# PowerBoard.net
KiCad netlist of a schematic drawn in Altium Designer
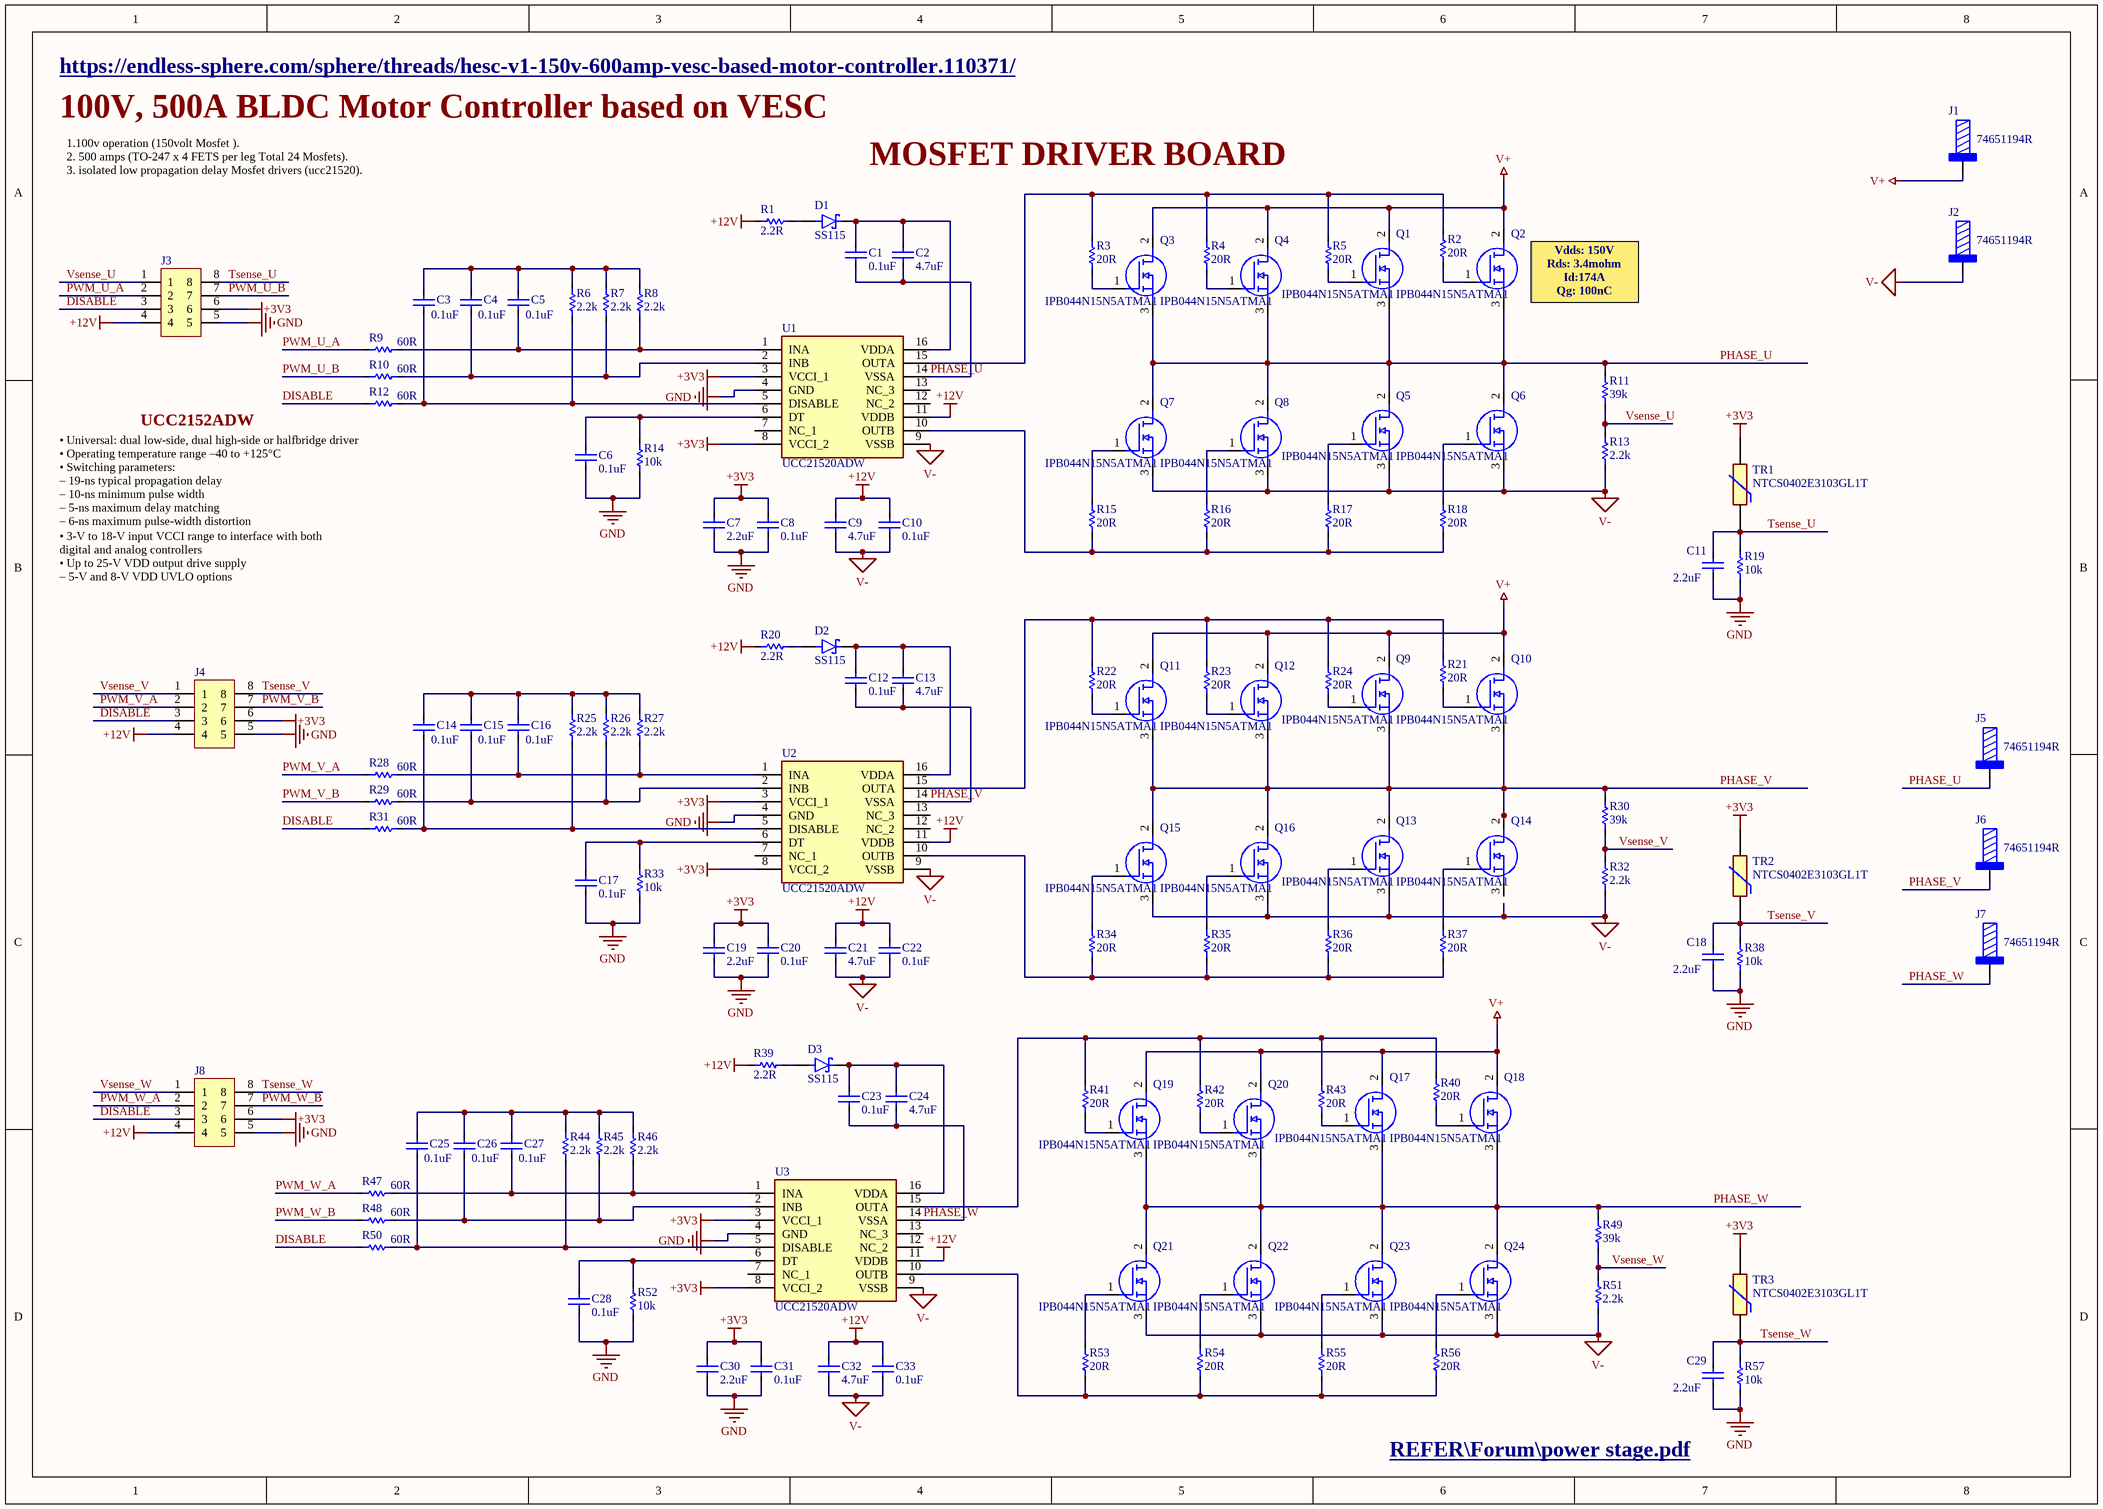
[diagram p0: PowerBoard.SchDoc]

(export (version "E")
  (design (tool "Eeschema 10.0.6"))
  (components
    (comp (ref "C1")
      (value "0.1uF")
      (footprint "SMD_C(0402)")
      (description "Multilayer Ceramic Capacitors MLCC - SMD/SMT 50 V 0.1uF X7R 0603 10%")
      (fields
        (field (name "MANUFACTURER") "Yageo")
        (field (name "MANUFACTURER PART NUMBER") "CC0603KPX7R9BB104")
      )
      (libsource (lib "CameraBoard") (part "Cap_1"))
    )
    (comp (ref "C2")
      (value "4.7uF")
      (footprint "SMD_C(0603)")
      (description "PHE840MA6100MA04R17")
      (fields
        (field (name "MANUFACTURER") "Yageo")
        (field (name "MANUFACTURER PART NUMBER") "CC0603KPX7R9BB104")
      )
      (libsource (lib "CameraBoard") (part "Cap_10"))
    )
    (comp (ref "C3")
      (value "0.1uF")
      (footprint "SMD_C(0402)")
      (description "Multilayer Ceramic Capacitors MLCC - SMD/SMT 50 V 0.1uF X7R 0603 10%")
      (fields
        (field (name "MANUFACTURER") "Yageo")
        (field (name "MANUFACTURER PART NUMBER") "CC0603KPX7R9BB104")
      )
      (libsource (lib "CameraBoard") (part "Cap_1"))
    )
    (comp (ref "C4")
      (value "0.1uF")
      (footprint "SMD_C(0402)")
      (description "Multilayer Ceramic Capacitors MLCC - SMD/SMT 50 V 0.1uF X7R 0603 10%")
      (fields
        (field (name "MANUFACTURER") "Yageo")
        (field (name "MANUFACTURER PART NUMBER") "CC0603KPX7R9BB104")
      )
      (libsource (lib "CameraBoard") (part "Cap_1"))
    )
    (comp (ref "C5")
      (value "0.1uF")
      (footprint "SMD_C(0402)")
      (description "Multilayer Ceramic Capacitors MLCC - SMD/SMT 50 V 0.1uF X7R 0603 10%")
      (fields
        (field (name "MANUFACTURER") "Yageo")
        (field (name "MANUFACTURER PART NUMBER") "CC0603KPX7R9BB104")
      )
      (libsource (lib "CameraBoard") (part "Cap_1"))
    )
    (comp (ref "C6")
      (value "0.1uF")
      (footprint "SMD_C(0402)")
      (description "Multilayer Ceramic Capacitors MLCC - SMD/SMT 50 V 0.1uF X7R 0603 10%")
      (fields
        (field (name "MANUFACTURER") "Yageo")
        (field (name "MANUFACTURER PART NUMBER") "CC0603KPX7R9BB104")
      )
      (libsource (lib "CameraBoard") (part "Cap_1"))
    )
    (comp (ref "C7")
      (value "2.2uF")
      (footprint "SMD_C(0603)")
      (description "PHE840MA6100MA04R17")
      (fields
        (field (name "MANUFACTURER") "Yageo")
        (field (name "MANUFACTURER PART NUMBER") "CC0603KPX7R9BB104")
      )
      (libsource (lib "CameraBoard") (part "Cap_10"))
    )
    (comp (ref "C8")
      (value "0.1uF")
      (footprint "SMD_C(0402)")
      (description "Multilayer Ceramic Capacitors MLCC - SMD/SMT 50 V 0.1uF X7R 0603 10%")
      (fields
        (field (name "MANUFACTURER") "Yageo")
        (field (name "MANUFACTURER PART NUMBER") "CC0603KPX7R9BB104")
      )
      (libsource (lib "CameraBoard") (part "Cap_1"))
    )
    (comp (ref "C9")
      (value "4.7uF")
      (footprint "SMD_C(0603)")
      (description "PHE840MA6100MA04R17")
      (fields
        (field (name "MANUFACTURER") "Yageo")
        (field (name "MANUFACTURER PART NUMBER") "CC0603KPX7R9BB104")
      )
      (libsource (lib "CameraBoard") (part "Cap_10"))
    )
    (comp (ref "C10")
      (value "0.1uF")
      (footprint "SMD_C(0402)")
      (description "Multilayer Ceramic Capacitors MLCC - SMD/SMT 50 V 0.1uF X7R 0603 10%")
      (fields
        (field (name "MANUFACTURER") "Yageo")
        (field (name "MANUFACTURER PART NUMBER") "CC0603KPX7R9BB104")
      )
      (libsource (lib "CameraBoard") (part "Cap_1"))
    )
    (comp (ref "C11")
      (value "2.2uF")
      (footprint "SMD_C(0402)")
      (description "Multilayer Ceramic Capacitors MLCC - SMD/SMT 50 V 0.1uF X7R 0603 10%")
      (libsource (lib "CameraBoard") (part "Cap_1"))
    )
    (comp (ref "C12")
      (value "0.1uF")
      (footprint "SMD_C(0402)")
      (description "Multilayer Ceramic Capacitors MLCC - SMD/SMT 50 V 0.1uF X7R 0603 10%")
      (fields
        (field (name "MANUFACTURER") "Yageo")
        (field (name "MANUFACTURER PART NUMBER") "CC0603KPX7R9BB104")
      )
      (libsource (lib "CameraBoard") (part "Cap_1"))
    )
    (comp (ref "C13")
      (value "4.7uF")
      (footprint "SMD_C(0603)")
      (description "PHE840MA6100MA04R17")
      (fields
        (field (name "MANUFACTURER") "Yageo")
        (field (name "MANUFACTURER PART NUMBER") "CC0603KPX7R9BB104")
      )
      (libsource (lib "CameraBoard") (part "Cap_10"))
    )
    (comp (ref "C14")
      (value "0.1uF")
      (footprint "SMD_C(0402)")
      (description "Multilayer Ceramic Capacitors MLCC - SMD/SMT 50 V 0.1uF X7R 0603 10%")
      (fields
        (field (name "MANUFACTURER") "Yageo")
        (field (name "MANUFACTURER PART NUMBER") "CC0603KPX7R9BB104")
      )
      (libsource (lib "CameraBoard") (part "Cap_1"))
    )
    (comp (ref "C15")
      (value "0.1uF")
      (footprint "SMD_C(0402)")
      (description "Multilayer Ceramic Capacitors MLCC - SMD/SMT 50 V 0.1uF X7R 0603 10%")
      (fields
        (field (name "MANUFACTURER") "Yageo")
        (field (name "MANUFACTURER PART NUMBER") "CC0603KPX7R9BB104")
      )
      (libsource (lib "CameraBoard") (part "Cap_1"))
    )
    (comp (ref "C16")
      (value "0.1uF")
      (footprint "SMD_C(0402)")
      (description "Multilayer Ceramic Capacitors MLCC - SMD/SMT 50 V 0.1uF X7R 0603 10%")
      (fields
        (field (name "MANUFACTURER") "Yageo")
        (field (name "MANUFACTURER PART NUMBER") "CC0603KPX7R9BB104")
      )
      (libsource (lib "CameraBoard") (part "Cap_1"))
    )
    (comp (ref "C17")
      (value "0.1uF")
      (footprint "SMD_C(0402)")
      (description "Multilayer Ceramic Capacitors MLCC - SMD/SMT 50 V 0.1uF X7R 0603 10%")
      (fields
        (field (name "MANUFACTURER") "Yageo")
        (field (name "MANUFACTURER PART NUMBER") "CC0603KPX7R9BB104")
      )
      (libsource (lib "CameraBoard") (part "Cap_1"))
    )
    (comp (ref "C18")
      (value "2.2uF")
      (footprint "SMD_C(0402)")
      (description "Multilayer Ceramic Capacitors MLCC - SMD/SMT 50 V 0.1uF X7R 0603 10%")
      (libsource (lib "CameraBoard") (part "Cap_1"))
    )
    (comp (ref "C19")
      (value "2.2uF")
      (footprint "SMD_C(0603)")
      (description "PHE840MA6100MA04R17")
      (fields
        (field (name "MANUFACTURER") "Yageo")
        (field (name "MANUFACTURER PART NUMBER") "CC0603KPX7R9BB104")
      )
      (libsource (lib "CameraBoard") (part "Cap_10"))
    )
    (comp (ref "C20")
      (value "0.1uF")
      (footprint "SMD_C(0402)")
      (description "Multilayer Ceramic Capacitors MLCC - SMD/SMT 50 V 0.1uF X7R 0603 10%")
      (fields
        (field (name "MANUFACTURER") "Yageo")
        (field (name "MANUFACTURER PART NUMBER") "CC0603KPX7R9BB104")
      )
      (libsource (lib "CameraBoard") (part "Cap_1"))
    )
    (comp (ref "C21")
      (value "4.7uF")
      (footprint "SMD_C(0603)")
      (description "PHE840MA6100MA04R17")
      (fields
        (field (name "MANUFACTURER") "Yageo")
        (field (name "MANUFACTURER PART NUMBER") "CC0603KPX7R9BB104")
      )
      (libsource (lib "CameraBoard") (part "Cap_10"))
    )
    (comp (ref "C22")
      (value "0.1uF")
      (footprint "SMD_C(0402)")
      (description "Multilayer Ceramic Capacitors MLCC - SMD/SMT 50 V 0.1uF X7R 0603 10%")
      (fields
        (field (name "MANUFACTURER") "Yageo")
        (field (name "MANUFACTURER PART NUMBER") "CC0603KPX7R9BB104")
      )
      (libsource (lib "CameraBoard") (part "Cap_1"))
    )
    (comp (ref "C23")
      (value "0.1uF")
      (footprint "SMD_C(0402)")
      (description "Multilayer Ceramic Capacitors MLCC - SMD/SMT 50 V 0.1uF X7R 0603 10%")
      (fields
        (field (name "MANUFACTURER") "Yageo")
        (field (name "MANUFACTURER PART NUMBER") "CC0603KPX7R9BB104")
      )
      (libsource (lib "CameraBoard") (part "Cap_1"))
    )
    (comp (ref "C24")
      (value "4.7uF")
      (footprint "SMD_C(0603)")
      (description "PHE840MA6100MA04R17")
      (fields
        (field (name "MANUFACTURER") "Yageo")
        (field (name "MANUFACTURER PART NUMBER") "CC0603KPX7R9BB104")
      )
      (libsource (lib "CameraBoard") (part "Cap_10"))
    )
    (comp (ref "C25")
      (value "0.1uF")
      (footprint "SMD_C(0402)")
      (description "Multilayer Ceramic Capacitors MLCC - SMD/SMT 50 V 0.1uF X7R 0603 10%")
      (fields
        (field (name "MANUFACTURER") "Yageo")
        (field (name "MANUFACTURER PART NUMBER") "CC0603KPX7R9BB104")
      )
      (libsource (lib "CameraBoard") (part "Cap_1"))
    )
    (comp (ref "C26")
      (value "0.1uF")
      (footprint "SMD_C(0402)")
      (description "Multilayer Ceramic Capacitors MLCC - SMD/SMT 50 V 0.1uF X7R 0603 10%")
      (fields
        (field (name "MANUFACTURER") "Yageo")
        (field (name "MANUFACTURER PART NUMBER") "CC0603KPX7R9BB104")
      )
      (libsource (lib "CameraBoard") (part "Cap_1"))
    )
    (comp (ref "C27")
      (value "0.1uF")
      (footprint "SMD_C(0402)")
      (description "Multilayer Ceramic Capacitors MLCC - SMD/SMT 50 V 0.1uF X7R 0603 10%")
      (fields
        (field (name "MANUFACTURER") "Yageo")
        (field (name "MANUFACTURER PART NUMBER") "CC0603KPX7R9BB104")
      )
      (libsource (lib "CameraBoard") (part "Cap_1"))
    )
    (comp (ref "C28")
      (value "0.1uF")
      (footprint "SMD_C(0402)")
      (description "Multilayer Ceramic Capacitors MLCC - SMD/SMT 50 V 0.1uF X7R 0603 10%")
      (fields
        (field (name "MANUFACTURER") "Yageo")
        (field (name "MANUFACTURER PART NUMBER") "CC0603KPX7R9BB104")
      )
      (libsource (lib "CameraBoard") (part "Cap_1"))
    )
    (comp (ref "C29")
      (value "2.2uF")
      (footprint "SMD_C(0402)")
      (description "Multilayer Ceramic Capacitors MLCC - SMD/SMT 50 V 0.1uF X7R 0603 10%")
      (libsource (lib "CameraBoard") (part "Cap_1"))
    )
    (comp (ref "C30")
      (value "2.2uF")
      (footprint "SMD_C(0603)")
      (description "PHE840MA6100MA04R17")
      (fields
        (field (name "MANUFACTURER") "Yageo")
        (field (name "MANUFACTURER PART NUMBER") "CC0603KPX7R9BB104")
      )
      (libsource (lib "CameraBoard") (part "Cap_10"))
    )
    (comp (ref "C31")
      (value "0.1uF")
      (footprint "SMD_C(0402)")
      (description "Multilayer Ceramic Capacitors MLCC - SMD/SMT 50 V 0.1uF X7R 0603 10%")
      (fields
        (field (name "MANUFACTURER") "Yageo")
        (field (name "MANUFACTURER PART NUMBER") "CC0603KPX7R9BB104")
      )
      (libsource (lib "CameraBoard") (part "Cap_1"))
    )
    (comp (ref "C32")
      (value "4.7uF")
      (footprint "SMD_C(0603)")
      (description "PHE840MA6100MA04R17")
      (fields
        (field (name "MANUFACTURER") "Yageo")
        (field (name "MANUFACTURER PART NUMBER") "CC0603KPX7R9BB104")
      )
      (libsource (lib "CameraBoard") (part "Cap_10"))
    )
    (comp (ref "C33")
      (value "0.1uF")
      (footprint "SMD_C(0402)")
      (description "Multilayer Ceramic Capacitors MLCC - SMD/SMT 50 V 0.1uF X7R 0603 10%")
      (fields
        (field (name "MANUFACTURER") "Yageo")
        (field (name "MANUFACTURER PART NUMBER") "CC0603KPX7R9BB104")
      )
      (libsource (lib "CameraBoard") (part "Cap_1"))
    )
    (comp (ref "D1")
      (value "SS115")
      (footprint "DIOM4325X250N")
      (description "1A, 150V, Schottky Rectifier")
      (fields (field (name "MF") "Taiwan Semiconductor"))
      (libsource (lib "SS115") (part "SS115"))
    )
    (comp (ref "D2")
      (value "SS115")
      (footprint "DIOM4325X250N")
      (description "1A, 150V, Schottky Rectifier")
      (fields (field (name "MF") "Taiwan Semiconductor"))
      (libsource (lib "SS115") (part "SS115"))
    )
    (comp (ref "D3")
      (value "SS115")
      (footprint "DIOM4325X250N")
      (description "1A, 150V, Schottky Rectifier")
      (fields (field (name "MF") "Taiwan Semiconductor"))
      (libsource (lib "SS115") (part "SS115"))
    )
    (comp (ref "J1")
      (value "74651194R")
      (footprint "74651194")
      (description "WP-THRSH REDCUBE THR with external thread, M4 x 5mm, 85A")
      (fields (field (name "MANUFACTURER") "Wurth Elektronik"))
      (libsource (lib "WP-THRSH") (part "74651194R"))
    )
    (comp (ref "J2")
      (value "74651194R")
      (footprint "74651194")
      (description "WP-THRSH REDCUBE THR with external thread, M4 x 5mm, 85A")
      (fields (field (name "MANUFACTURER") "Wurth Elektronik"))
      (libsource (lib "WP-THRSH") (part "74651194R"))
    )
    (comp (ref "J3")
      (value "~")
      (footprint "*")
      (description "2 Row 2.54mm Pitch 8 pins")
      (libsource (lib "VESC_MotorController") (part "PCB Header"))
    )
    (comp (ref "J4")
      (value "~")
      (footprint "*")
      (description "2 Row 2.54mm Pitch 8 pins")
      (libsource (lib "VESC_MotorController") (part "PCB Header"))
    )
    (comp (ref "J5")
      (value "74651194R")
      (footprint "74651194")
      (description "WP-THRSH REDCUBE THR with external thread, M4 x 5mm, 85A")
      (fields (field (name "MANUFACTURER") "Wurth Elektronik"))
      (libsource (lib "WP-THRSH") (part "74651194R"))
    )
    (comp (ref "J6")
      (value "74651194R")
      (footprint "74651194")
      (description "WP-THRSH REDCUBE THR with external thread, M4 x 5mm, 85A")
      (fields (field (name "MANUFACTURER") "Wurth Elektronik"))
      (libsource (lib "WP-THRSH") (part "74651194R"))
    )
    (comp (ref "J7")
      (value "74651194R")
      (footprint "74651194")
      (description "WP-THRSH REDCUBE THR with external thread, M4 x 5mm, 85A")
      (fields (field (name "MANUFACTURER") "Wurth Elektronik"))
      (libsource (lib "WP-THRSH") (part "74651194R"))
    )
    (comp (ref "J8")
      (value "~")
      (footprint "*")
      (description "2 Row 2.54mm Pitch 8 pins")
      (libsource (lib "VESC_MotorController") (part "PCB Header"))
    )
    (comp (ref "Q1")
      (value "IPB044N15N5ATMA1")
      (footprint "TO546P531X1558X2499-3P")
      (description "MOSFET N-CHANNEL 100+")
      (fields
        (field (name "MOUSER PART NUMBER") "942-AUIRFP4568")
        (field (name "MANUFACTURER_PART_NUMBER") "AUIRFP4568")
      )
      (libsource (lib "AUIRFP4568") (part "AUIRFP4568"))
    )
    (comp (ref "Q2")
      (value "IPB044N15N5ATMA1")
      (footprint "TO546P531X1558X2499-3P")
      (description "MOSFET N-CHANNEL 100+")
      (fields
        (field (name "MOUSER PART NUMBER") "942-AUIRFP4568")
        (field (name "MANUFACTURER_PART_NUMBER") "AUIRFP4568")
      )
      (libsource (lib "AUIRFP4568") (part "AUIRFP4568"))
    )
    (comp (ref "Q3")
      (value "IPB044N15N5ATMA1")
      (footprint "TO546P531X1558X2499-3P")
      (description "MOSFET N-CHANNEL 100+")
      (fields
        (field (name "MOUSER PART NUMBER") "942-AUIRFP4568")
        (field (name "MANUFACTURER_PART_NUMBER") "AUIRFP4568")
      )
      (libsource (lib "AUIRFP4568") (part "AUIRFP4568"))
    )
    (comp (ref "Q4")
      (value "IPB044N15N5ATMA1")
      (footprint "TO546P531X1558X2499-3P")
      (description "MOSFET N-CHANNEL 100+")
      (fields
        (field (name "MOUSER PART NUMBER") "942-AUIRFP4568")
        (field (name "MANUFACTURER_PART_NUMBER") "AUIRFP4568")
      )
      (libsource (lib "AUIRFP4568") (part "AUIRFP4568"))
    )
    (comp (ref "Q5")
      (value "IPB044N15N5ATMA1")
      (footprint "TO546P531X1558X2499-3P")
      (description "MOSFET N-CHANNEL 100+")
      (fields
        (field (name "MOUSER PART NUMBER") "942-AUIRFP4568")
        (field (name "MANUFACTURER_PART_NUMBER") "AUIRFP4568")
      )
      (libsource (lib "AUIRFP4568") (part "AUIRFP4568"))
    )
    (comp (ref "Q6")
      (value "IPB044N15N5ATMA1")
      (footprint "TO546P531X1558X2499-3P")
      (description "MOSFET N-CHANNEL 100+")
      (fields
        (field (name "MOUSER PART NUMBER") "942-AUIRFP4568")
        (field (name "MANUFACTURER_PART_NUMBER") "AUIRFP4568")
      )
      (libsource (lib "AUIRFP4568") (part "AUIRFP4568"))
    )
    (comp (ref "Q7")
      (value "IPB044N15N5ATMA1")
      (footprint "TO546P531X1558X2499-3P")
      (description "MOSFET N-CHANNEL 100+")
      (fields
        (field (name "MOUSER PART NUMBER") "942-AUIRFP4568")
        (field (name "MANUFACTURER_PART_NUMBER") "AUIRFP4568")
      )
      (libsource (lib "AUIRFP4568") (part "AUIRFP4568"))
    )
    (comp (ref "Q8")
      (value "IPB044N15N5ATMA1")
      (footprint "TO546P531X1558X2499-3P")
      (description "MOSFET N-CHANNEL 100+")
      (fields
        (field (name "MOUSER PART NUMBER") "942-AUIRFP4568")
        (field (name "MANUFACTURER_PART_NUMBER") "AUIRFP4568")
      )
      (libsource (lib "AUIRFP4568") (part "AUIRFP4568"))
    )
    (comp (ref "Q9")
      (value "IPB044N15N5ATMA1")
      (footprint "TO546P531X1558X2499-3P")
      (description "MOSFET N-CHANNEL 100+")
      (fields
        (field (name "MOUSER PART NUMBER") "942-AUIRFP4568")
        (field (name "MANUFACTURER_PART_NUMBER") "AUIRFP4568")
      )
      (libsource (lib "AUIRFP4568") (part "AUIRFP4568"))
    )
    (comp (ref "Q10")
      (value "IPB044N15N5ATMA1")
      (footprint "TO546P531X1558X2499-3P")
      (description "MOSFET N-CHANNEL 100+")
      (fields
        (field (name "MOUSER PART NUMBER") "942-AUIRFP4568")
        (field (name "MANUFACTURER_PART_NUMBER") "AUIRFP4568")
      )
      (libsource (lib "AUIRFP4568") (part "AUIRFP4568"))
    )
    (comp (ref "Q11")
      (value "IPB044N15N5ATMA1")
      (footprint "TO546P531X1558X2499-3P")
      (description "MOSFET N-CHANNEL 100+")
      (fields
        (field (name "MOUSER PART NUMBER") "942-AUIRFP4568")
        (field (name "MANUFACTURER_PART_NUMBER") "AUIRFP4568")
      )
      (libsource (lib "AUIRFP4568") (part "AUIRFP4568"))
    )
    (comp (ref "Q12")
      (value "IPB044N15N5ATMA1")
      (footprint "TO546P531X1558X2499-3P")
      (description "MOSFET N-CHANNEL 100+")
      (fields
        (field (name "MOUSER PART NUMBER") "942-AUIRFP4568")
        (field (name "MANUFACTURER_PART_NUMBER") "AUIRFP4568")
      )
      (libsource (lib "AUIRFP4568") (part "AUIRFP4568"))
    )
    (comp (ref "Q13")
      (value "IPB044N15N5ATMA1")
      (footprint "TO546P531X1558X2499-3P")
      (description "MOSFET N-CHANNEL 100+")
      (fields
        (field (name "MOUSER PART NUMBER") "942-AUIRFP4568")
        (field (name "MANUFACTURER_PART_NUMBER") "AUIRFP4568")
      )
      (libsource (lib "AUIRFP4568") (part "AUIRFP4568"))
    )
    (comp (ref "Q14")
      (value "IPB044N15N5ATMA1")
      (footprint "TO546P531X1558X2499-3P")
      (description "MOSFET N-CHANNEL 100+")
      (fields
        (field (name "MOUSER PART NUMBER") "942-AUIRFP4568")
        (field (name "MANUFACTURER_PART_NUMBER") "AUIRFP4568")
      )
      (libsource (lib "AUIRFP4568") (part "AUIRFP4568"))
    )
    (comp (ref "Q15")
      (value "IPB044N15N5ATMA1")
      (footprint "TO546P531X1558X2499-3P")
      (description "MOSFET N-CHANNEL 100+")
      (fields
        (field (name "MOUSER PART NUMBER") "942-AUIRFP4568")
        (field (name "MANUFACTURER_PART_NUMBER") "AUIRFP4568")
      )
      (libsource (lib "AUIRFP4568") (part "AUIRFP4568"))
    )
    (comp (ref "Q16")
      (value "IPB044N15N5ATMA1")
      (footprint "TO546P531X1558X2499-3P")
      (description "MOSFET N-CHANNEL 100+")
      (fields
        (field (name "MOUSER PART NUMBER") "942-AUIRFP4568")
        (field (name "MANUFACTURER_PART_NUMBER") "AUIRFP4568")
      )
      (libsource (lib "AUIRFP4568") (part "AUIRFP4568"))
    )
    (comp (ref "Q17")
      (value "IPB044N15N5ATMA1")
      (footprint "TO546P531X1558X2499-3P")
      (description "MOSFET N-CHANNEL 100+")
      (fields
        (field (name "MOUSER PART NUMBER") "942-AUIRFP4568")
        (field (name "MANUFACTURER_PART_NUMBER") "AUIRFP4568")
      )
      (libsource (lib "AUIRFP4568") (part "AUIRFP4568"))
    )
    (comp (ref "Q18")
      (value "IPB044N15N5ATMA1")
      (footprint "TO546P531X1558X2499-3P")
      (description "MOSFET N-CHANNEL 100+")
      (fields
        (field (name "MOUSER PART NUMBER") "942-AUIRFP4568")
        (field (name "MANUFACTURER_PART_NUMBER") "AUIRFP4568")
      )
      (libsource (lib "AUIRFP4568") (part "AUIRFP4568"))
    )
    (comp (ref "Q19")
      (value "IPB044N15N5ATMA1")
      (footprint "TO546P531X1558X2499-3P")
      (description "MOSFET N-CHANNEL 100+")
      (fields
        (field (name "MOUSER PART NUMBER") "942-AUIRFP4568")
        (field (name "MANUFACTURER_PART_NUMBER") "AUIRFP4568")
      )
      (libsource (lib "AUIRFP4568") (part "AUIRFP4568"))
    )
    (comp (ref "Q20")
      (value "IPB044N15N5ATMA1")
      (footprint "TO546P531X1558X2499-3P")
      (description "MOSFET N-CHANNEL 100+")
      (fields
        (field (name "MOUSER PART NUMBER") "942-AUIRFP4568")
        (field (name "MANUFACTURER_PART_NUMBER") "AUIRFP4568")
      )
      (libsource (lib "AUIRFP4568") (part "AUIRFP4568"))
    )
    (comp (ref "Q21")
      (value "IPB044N15N5ATMA1")
      (footprint "TO546P531X1558X2499-3P")
      (description "MOSFET N-CHANNEL 100+")
      (fields
        (field (name "MOUSER PART NUMBER") "942-AUIRFP4568")
        (field (name "MANUFACTURER_PART_NUMBER") "AUIRFP4568")
      )
      (libsource (lib "AUIRFP4568") (part "AUIRFP4568"))
    )
    (comp (ref "Q22")
      (value "IPB044N15N5ATMA1")
      (footprint "TO546P531X1558X2499-3P")
      (description "MOSFET N-CHANNEL 100+")
      (fields
        (field (name "MOUSER PART NUMBER") "942-AUIRFP4568")
        (field (name "MANUFACTURER_PART_NUMBER") "AUIRFP4568")
      )
      (libsource (lib "AUIRFP4568") (part "AUIRFP4568"))
    )
    (comp (ref "Q23")
      (value "IPB044N15N5ATMA1")
      (footprint "TO546P531X1558X2499-3P")
      (description "MOSFET N-CHANNEL 100+")
      (fields
        (field (name "MOUSER PART NUMBER") "942-AUIRFP4568")
        (field (name "MANUFACTURER_PART_NUMBER") "AUIRFP4568")
      )
      (libsource (lib "AUIRFP4568") (part "AUIRFP4568"))
    )
    (comp (ref "Q24")
      (value "IPB044N15N5ATMA1")
      (footprint "TO546P531X1558X2499-3P")
      (description "MOSFET N-CHANNEL 100+")
      (fields
        (field (name "MOUSER PART NUMBER") "942-AUIRFP4568")
        (field (name "MANUFACTURER_PART_NUMBER") "AUIRFP4568")
      )
      (libsource (lib "AUIRFP4568") (part "AUIRFP4568"))
    )
    (comp (ref "R1")
      (value "2.2R")
      (footprint "SMD_R(0402)")
      (description "CRCW04024R02FKED")
      (fields (field (name "PUBLISHER") "Altium Limited"))
      (libsource (lib "CameraBoard") (part "Res Semi_1"))
    )
    (comp (ref "R2")
      (value "20R")
      (footprint "SMD_R(0402)")
      (description "CRCW04024R02FKED")
      (fields (field (name "PUBLISHER") "Altium Limited"))
      (libsource (lib "CameraBoard") (part "Res Semi_1"))
    )
    (comp (ref "R3")
      (value "20R")
      (footprint "SMD_R(0402)")
      (description "CRCW04024R02FKED")
      (fields (field (name "PUBLISHER") "Altium Limited"))
      (libsource (lib "CameraBoard") (part "Res Semi_1"))
    )
    (comp (ref "R4")
      (value "20R")
      (footprint "SMD_R(0402)")
      (description "CRCW04024R02FKED")
      (fields (field (name "PUBLISHER") "Altium Limited"))
      (libsource (lib "CameraBoard") (part "Res Semi_1"))
    )
    (comp (ref "R5")
      (value "20R")
      (footprint "SMD_R(0402)")
      (description "CRCW04024R02FKED")
      (fields (field (name "PUBLISHER") "Altium Limited"))
      (libsource (lib "CameraBoard") (part "Res Semi_1"))
    )
    (comp (ref "R6")
      (value "2.2k")
      (footprint "SMD_R(0402)")
      (description "CRCW04024R02FKED")
      (fields (field (name "PUBLISHER") "Altium Limited"))
      (libsource (lib "CameraBoard") (part "Res Semi_2"))
    )
    (comp (ref "R7")
      (value "2.2k")
      (footprint "SMD_R(0402)")
      (description "CRCW04024R02FKED")
      (fields (field (name "PUBLISHER") "Altium Limited"))
      (libsource (lib "CameraBoard") (part "Res Semi_2"))
    )
    (comp (ref "R8")
      (value "2.2k")
      (footprint "SMD_R(0402)")
      (description "CRCW04024R02FKED")
      (fields (field (name "PUBLISHER") "Altium Limited"))
      (libsource (lib "CameraBoard") (part "Res Semi_2"))
    )
    (comp (ref "R9")
      (value "60R")
      (footprint "SMD_R(0402)")
      (description "CRCW04024R02FKED")
      (fields (field (name "PUBLISHER") "Altium Limited"))
      (libsource (lib "CameraBoard") (part "Res Semi_1"))
    )
    (comp (ref "R10")
      (value "60R")
      (footprint "SMD_R(0402)")
      (description "CRCW04024R02FKED")
      (fields (field (name "PUBLISHER") "Altium Limited"))
      (libsource (lib "CameraBoard") (part "Res Semi_1"))
    )
    (comp (ref "R11")
      (value "39k")
      (footprint "SMD_R(0402)")
      (description "CRCW04024R02FKED")
      (fields (field (name "PUBLISHER") "Altium Limited"))
      (libsource (lib "CameraBoard") (part "Res Semi_5"))
    )
    (comp (ref "R12")
      (value "60R")
      (footprint "SMD_R(0402)")
      (description "CRCW04024R02FKED")
      (fields (field (name "PUBLISHER") "Altium Limited"))
      (libsource (lib "CameraBoard") (part "Res Semi_1"))
    )
    (comp (ref "R13")
      (value "2.2k")
      (footprint "SMD_R(0402)")
      (description "CRCW04024R02FKED")
      (fields (field (name "PUBLISHER") "Altium Limited"))
      (libsource (lib "CameraBoard") (part "Res Semi_5"))
    )
    (comp (ref "R14")
      (value "10k")
      (footprint "SMD_R(0402)")
      (description "CRCW04024R02FKED")
      (fields (field (name "PUBLISHER") "Altium Limited"))
      (libsource (lib "CameraBoard") (part "Res Semi_5"))
    )
    (comp (ref "R15")
      (value "20R")
      (footprint "SMD_R(0402)")
      (description "CRCW04024R02FKED")
      (fields (field (name "PUBLISHER") "Altium Limited"))
      (libsource (lib "CameraBoard") (part "Res Semi_1"))
    )
    (comp (ref "R16")
      (value "20R")
      (footprint "SMD_R(0402)")
      (description "CRCW04024R02FKED")
      (fields (field (name "PUBLISHER") "Altium Limited"))
      (libsource (lib "CameraBoard") (part "Res Semi_1"))
    )
    (comp (ref "R17")
      (value "20R")
      (footprint "SMD_R(0402)")
      (description "CRCW04024R02FKED")
      (fields (field (name "PUBLISHER") "Altium Limited"))
      (libsource (lib "CameraBoard") (part "Res Semi_1"))
    )
    (comp (ref "R18")
      (value "20R")
      (footprint "SMD_R(0402)")
      (description "CRCW04024R02FKED")
      (fields (field (name "PUBLISHER") "Altium Limited"))
      (libsource (lib "CameraBoard") (part "Res Semi_1"))
    )
    (comp (ref "R19")
      (value "10k")
      (footprint "SMD_R(0402)")
      (description "CRCW04024R02FKED")
      (fields (field (name "PUBLISHER") "Altium Limited"))
      (libsource (lib "CameraBoard") (part "Res Semi_5"))
    )
    (comp (ref "R20")
      (value "2.2R")
      (footprint "SMD_R(0402)")
      (description "CRCW04024R02FKED")
      (fields (field (name "PUBLISHER") "Altium Limited"))
      (libsource (lib "CameraBoard") (part "Res Semi_1"))
    )
    (comp (ref "R21")
      (value "20R")
      (footprint "SMD_R(0402)")
      (description "CRCW04024R02FKED")
      (fields (field (name "PUBLISHER") "Altium Limited"))
      (libsource (lib "CameraBoard") (part "Res Semi_1"))
    )
    (comp (ref "R22")
      (value "20R")
      (footprint "SMD_R(0402)")
      (description "CRCW04024R02FKED")
      (fields (field (name "PUBLISHER") "Altium Limited"))
      (libsource (lib "CameraBoard") (part "Res Semi_1"))
    )
    (comp (ref "R23")
      (value "20R")
      (footprint "SMD_R(0402)")
      (description "CRCW04024R02FKED")
      (fields (field (name "PUBLISHER") "Altium Limited"))
      (libsource (lib "CameraBoard") (part "Res Semi_1"))
    )
    (comp (ref "R24")
      (value "20R")
      (footprint "SMD_R(0402)")
      (description "CRCW04024R02FKED")
      (fields (field (name "PUBLISHER") "Altium Limited"))
      (libsource (lib "CameraBoard") (part "Res Semi_1"))
    )
    (comp (ref "R25")
      (value "2.2k")
      (footprint "SMD_R(0402)")
      (description "CRCW04024R02FKED")
      (fields (field (name "PUBLISHER") "Altium Limited"))
      (libsource (lib "CameraBoard") (part "Res Semi_2"))
    )
    (comp (ref "R26")
      (value "2.2k")
      (footprint "SMD_R(0402)")
      (description "CRCW04024R02FKED")
      (fields (field (name "PUBLISHER") "Altium Limited"))
      (libsource (lib "CameraBoard") (part "Res Semi_2"))
    )
    (comp (ref "R27")
      (value "2.2k")
      (footprint "SMD_R(0402)")
      (description "CRCW04024R02FKED")
      (fields (field (name "PUBLISHER") "Altium Limited"))
      (libsource (lib "CameraBoard") (part "Res Semi_2"))
    )
    (comp (ref "R28")
      (value "60R")
      (footprint "SMD_R(0402)")
      (description "CRCW04024R02FKED")
      (fields (field (name "PUBLISHER") "Altium Limited"))
      (libsource (lib "CameraBoard") (part "Res Semi_1"))
    )
    (comp (ref "R29")
      (value "60R")
      (footprint "SMD_R(0402)")
      (description "CRCW04024R02FKED")
      (fields (field (name "PUBLISHER") "Altium Limited"))
      (libsource (lib "CameraBoard") (part "Res Semi_1"))
    )
    (comp (ref "R30")
      (value "39k")
      (footprint "SMD_R(0402)")
      (description "CRCW04024R02FKED")
      (fields (field (name "PUBLISHER") "Altium Limited"))
      (libsource (lib "CameraBoard") (part "Res Semi_5"))
    )
    (comp (ref "R31")
      (value "60R")
      (footprint "SMD_R(0402)")
      (description "CRCW04024R02FKED")
      (fields (field (name "PUBLISHER") "Altium Limited"))
      (libsource (lib "CameraBoard") (part "Res Semi_1"))
    )
    (comp (ref "R32")
      (value "2.2k")
      (footprint "SMD_R(0402)")
      (description "CRCW04024R02FKED")
      (fields (field (name "PUBLISHER") "Altium Limited"))
      (libsource (lib "CameraBoard") (part "Res Semi_5"))
    )
    (comp (ref "R33")
      (value "10k")
      (footprint "SMD_R(0402)")
      (description "CRCW04024R02FKED")
      (fields (field (name "PUBLISHER") "Altium Limited"))
      (libsource (lib "CameraBoard") (part "Res Semi_5"))
    )
    (comp (ref "R34")
      (value "20R")
      (footprint "SMD_R(0402)")
      (description "CRCW04024R02FKED")
      (fields (field (name "PUBLISHER") "Altium Limited"))
      (libsource (lib "CameraBoard") (part "Res Semi_1"))
    )
    (comp (ref "R35")
      (value "20R")
      (footprint "SMD_R(0402)")
      (description "CRCW04024R02FKED")
      (fields (field (name "PUBLISHER") "Altium Limited"))
      (libsource (lib "CameraBoard") (part "Res Semi_1"))
    )
    (comp (ref "R36")
      (value "20R")
      (footprint "SMD_R(0402)")
      (description "CRCW04024R02FKED")
      (fields (field (name "PUBLISHER") "Altium Limited"))
      (libsource (lib "CameraBoard") (part "Res Semi_1"))
    )
    (comp (ref "R37")
      (value "20R")
      (footprint "SMD_R(0402)")
      (description "CRCW04024R02FKED")
      (fields (field (name "PUBLISHER") "Altium Limited"))
      (libsource (lib "CameraBoard") (part "Res Semi_1"))
    )
    (comp (ref "R38")
      (value "10k")
      (footprint "SMD_R(0402)")
      (description "CRCW04024R02FKED")
      (fields (field (name "PUBLISHER") "Altium Limited"))
      (libsource (lib "CameraBoard") (part "Res Semi_5"))
    )
    (comp (ref "R39")
      (value "2.2R")
      (footprint "SMD_R(0402)")
      (description "CRCW04024R02FKED")
      (fields (field (name "PUBLISHER") "Altium Limited"))
      (libsource (lib "CameraBoard") (part "Res Semi_1"))
    )
    (comp (ref "R40")
      (value "20R")
      (footprint "SMD_R(0402)")
      (description "CRCW04024R02FKED")
      (fields (field (name "PUBLISHER") "Altium Limited"))
      (libsource (lib "CameraBoard") (part "Res Semi_1"))
    )
    (comp (ref "R41")
      (value "20R")
      (footprint "SMD_R(0402)")
      (description "CRCW04024R02FKED")
      (fields (field (name "PUBLISHER") "Altium Limited"))
      (libsource (lib "CameraBoard") (part "Res Semi_1"))
    )
    (comp (ref "R42")
      (value "20R")
      (footprint "SMD_R(0402)")
      (description "CRCW04024R02FKED")
      (fields (field (name "PUBLISHER") "Altium Limited"))
      (libsource (lib "CameraBoard") (part "Res Semi_1"))
    )
    (comp (ref "R43")
      (value "20R")
      (footprint "SMD_R(0402)")
      (description "CRCW04024R02FKED")
      (fields (field (name "PUBLISHER") "Altium Limited"))
      (libsource (lib "CameraBoard") (part "Res Semi_1"))
    )
    (comp (ref "R44")
      (value "2.2k")
      (footprint "SMD_R(0402)")
      (description "CRCW04024R02FKED")
      (fields (field (name "PUBLISHER") "Altium Limited"))
      (libsource (lib "CameraBoard") (part "Res Semi_2"))
    )
    (comp (ref "R45")
      (value "2.2k")
      (footprint "SMD_R(0402)")
      (description "CRCW04024R02FKED")
      (fields (field (name "PUBLISHER") "Altium Limited"))
      (libsource (lib "CameraBoard") (part "Res Semi_2"))
    )
    (comp (ref "R46")
      (value "2.2k")
      (footprint "SMD_R(0402)")
      (description "CRCW04024R02FKED")
      (fields (field (name "PUBLISHER") "Altium Limited"))
      (libsource (lib "CameraBoard") (part "Res Semi_2"))
    )
    (comp (ref "R47")
      (value "60R")
      (footprint "SMD_R(0402)")
      (description "CRCW04024R02FKED")
      (fields (field (name "PUBLISHER") "Altium Limited"))
      (libsource (lib "CameraBoard") (part "Res Semi_1"))
    )
    (comp (ref "R48")
      (value "60R")
      (footprint "SMD_R(0402)")
      (description "CRCW04024R02FKED")
      (fields (field (name "PUBLISHER") "Altium Limited"))
      (libsource (lib "CameraBoard") (part "Res Semi_1"))
    )
    (comp (ref "R49")
      (value "39k")
      (footprint "SMD_R(0402)")
      (description "CRCW04024R02FKED")
      (fields (field (name "PUBLISHER") "Altium Limited"))
      (libsource (lib "CameraBoard") (part "Res Semi_5"))
    )
    (comp (ref "R50")
      (value "60R")
      (footprint "SMD_R(0402)")
      (description "CRCW04024R02FKED")
      (fields (field (name "PUBLISHER") "Altium Limited"))
      (libsource (lib "CameraBoard") (part "Res Semi_1"))
    )
    (comp (ref "R51")
      (value "2.2k")
      (footprint "SMD_R(0402)")
      (description "CRCW04024R02FKED")
      (fields (field (name "PUBLISHER") "Altium Limited"))
      (libsource (lib "CameraBoard") (part "Res Semi_5"))
    )
    (comp (ref "R52")
      (value "10k")
      (footprint "SMD_R(0402)")
      (description "CRCW04024R02FKED")
      (fields (field (name "PUBLISHER") "Altium Limited"))
      (libsource (lib "CameraBoard") (part "Res Semi_5"))
    )
    (comp (ref "R53")
      (value "20R")
      (footprint "SMD_R(0402)")
      (description "CRCW04024R02FKED")
      (fields (field (name "PUBLISHER") "Altium Limited"))
      (libsource (lib "CameraBoard") (part "Res Semi_1"))
    )
    (comp (ref "R54")
      (value "20R")
      (footprint "SMD_R(0402)")
      (description "CRCW04024R02FKED")
      (fields (field (name "PUBLISHER") "Altium Limited"))
      (libsource (lib "CameraBoard") (part "Res Semi_1"))
    )
    (comp (ref "R55")
      (value "20R")
      (footprint "SMD_R(0402)")
      (description "CRCW04024R02FKED")
      (fields (field (name "PUBLISHER") "Altium Limited"))
      (libsource (lib "CameraBoard") (part "Res Semi_1"))
    )
    (comp (ref "R56")
      (value "20R")
      (footprint "SMD_R(0402)")
      (description "CRCW04024R02FKED")
      (fields (field (name "PUBLISHER") "Altium Limited"))
      (libsource (lib "CameraBoard") (part "Res Semi_1"))
    )
    (comp (ref "R57")
      (value "10k")
      (footprint "SMD_R(0402)")
      (description "CRCW04024R02FKED")
      (fields (field (name "PUBLISHER") "Altium Limited"))
      (libsource (lib "CameraBoard") (part "Res Semi_5"))
    )
    (comp (ref "TR1")
      (value "NTCS0402E3103GL1T")
      (footprint "THRMC1005X65N")
      (description "NTC Thermistors 10Kohms 2% AEC-Q200")
      (fields (field (name "MOUSER PART NUMBER") "594-NTCS402E3103GL1T"))
      (libsource (lib "NTCS0402E3103GL1T") (part "NTCS0402E3103GL1T"))
    )
    (comp (ref "TR2")
      (value "NTCS0402E3103GL1T")
      (footprint "THRMC1005X65N")
      (description "NTC Thermistors 10Kohms 2% AEC-Q200")
      (fields (field (name "MOUSER PART NUMBER") "594-NTCS402E3103GL1T"))
      (libsource (lib "NTCS0402E3103GL1T") (part "NTCS0402E3103GL1T"))
    )
    (comp (ref "TR3")
      (value "NTCS0402E3103GL1T")
      (footprint "THRMC1005X65N")
      (description "NTC Thermistors 10Kohms 2% AEC-Q200")
      (fields (field (name "MOUSER PART NUMBER") "594-NTCS402E3103GL1T"))
      (libsource (lib "NTCS0402E3103GL1T") (part "NTCS0402E3103GL1T"))
    )
    (comp (ref "U1")
      (value "UCC21520ADW")
      (footprint "SOIC127P1030X265-16N")
      (description "4A/6A, 5.7 kVrms Isolated Dual Channel Gate Driver")
      (fields (field (name "MOUSER PART NUMBER") "595-UCC21520ADW"))
      (libsource (lib "UCC21520ADW") (part "UCC21520ADW"))
    )
    (comp (ref "U2")
      (value "UCC21520ADW")
      (footprint "SOIC127P1030X265-16N")
      (description "4A/6A, 5.7 kVrms Isolated Dual Channel Gate Driver")
      (fields (field (name "MOUSER PART NUMBER") "595-UCC21520ADW"))
      (libsource (lib "UCC21520ADW") (part "UCC21520ADW"))
    )
    (comp (ref "U3")
      (value "UCC21520ADW")
      (footprint "SOIC127P1030X265-16N")
      (description "4A/6A, 5.7 kVrms Isolated Dual Channel Gate Driver")
      (fields (field (name "MOUSER PART NUMBER") "595-UCC21520ADW"))
      (libsource (lib "UCC21520ADW") (part "UCC21520ADW"))
    )
  )
  (nets
    (net (code "1") (name "+3V3") (class "Default")
      (node (ref "C19") (pin "2") (pinfunction "2_2") (pintype "passive"))
      (node (ref "C20") (pin "2") (pinfunction "2_2") (pintype "passive"))
      (node (ref "C30") (pin "2") (pinfunction "2_2") (pintype "passive"))
      (node (ref "C31") (pin "2") (pinfunction "2_2") (pintype "passive"))
      (node (ref "C7") (pin "2") (pinfunction "2_2") (pintype "passive"))
      (node (ref "C8") (pin "2") (pinfunction "2_2") (pintype "passive"))
      (node (ref "J3") (pin "6") (pinfunction "6_6") (pintype "passive"))
      (node (ref "J4") (pin "6") (pinfunction "6_6") (pintype "passive"))
      (node (ref "J8") (pin "6") (pinfunction "6_6") (pintype "passive"))
      (node (ref "TR1") (pin "2") (pinfunction "2_2") (pintype "passive"))
      (node (ref "TR2") (pin "2") (pinfunction "2_2") (pintype "passive"))
      (node (ref "TR3") (pin "2") (pinfunction "2_2") (pintype "passive"))
      (node (ref "U1") (pin "3") (pinfunction "VCCI_1_3") (pintype "passive"))
      (node (ref "U1") (pin "8") (pinfunction "VCCI_2_8") (pintype "passive"))
      (node (ref "U2") (pin "3") (pinfunction "VCCI_1_3") (pintype "passive"))
      (node (ref "U2") (pin "8") (pinfunction "VCCI_2_8") (pintype "passive"))
      (node (ref "U3") (pin "3") (pinfunction "VCCI_1_3") (pintype "passive"))
      (node (ref "U3") (pin "8") (pinfunction "VCCI_2_8") (pintype "passive"))
    )
    (net (code "2") (name "+12V") (class "Default")
      (node (ref "C10") (pin "2") (pinfunction "2_2") (pintype "passive"))
      (node (ref "C21") (pin "2") (pinfunction "2_2") (pintype "passive"))
      (node (ref "C22") (pin "2") (pinfunction "2_2") (pintype "passive"))
      (node (ref "C32") (pin "2") (pinfunction "2_2") (pintype "passive"))
      (node (ref "C33") (pin "2") (pinfunction "2_2") (pintype "passive"))
      (node (ref "C9") (pin "2") (pinfunction "2_2") (pintype "passive"))
      (node (ref "J3") (pin "4") (pinfunction "4_4") (pintype "passive"))
      (node (ref "J4") (pin "4") (pinfunction "4_4") (pintype "passive"))
      (node (ref "J8") (pin "4") (pinfunction "4_4") (pintype "passive"))
      (node (ref "R1") (pin "1") (pinfunction "1_1") (pintype "passive"))
      (node (ref "R20") (pin "1") (pinfunction "1_1") (pintype "passive"))
      (node (ref "R39") (pin "1") (pinfunction "1_1") (pintype "passive"))
      (node (ref "U1") (pin "11") (pinfunction "VDDB_11") (pintype "passive"))
      (node (ref "U2") (pin "11") (pinfunction "VDDB_11") (pintype "passive"))
      (node (ref "U3") (pin "11") (pinfunction "VDDB_11") (pintype "passive"))
    )
    (net (code "3") (name "/DISABLE") (class "Default")
      (node (ref "J3") (pin "3") (pinfunction "3_3") (pintype "passive"))
      (node (ref "J4") (pin "3") (pinfunction "3_3") (pintype "passive"))
      (node (ref "J8") (pin "3") (pinfunction "3_3") (pintype "passive"))
      (node (ref "R12") (pin "1") (pinfunction "1_1") (pintype "passive"))
      (node (ref "R31") (pin "1") (pinfunction "1_1") (pintype "passive"))
      (node (ref "R50") (pin "1") (pinfunction "1_1") (pintype "passive"))
    )
    (net (code "4") (name "/PHASE_U") (class "Default")
      (node (ref "C1") (pin "1") (pinfunction "1_1") (pintype "passive"))
      (node (ref "C2") (pin "1") (pinfunction "1_1") (pintype "passive"))
      (node (ref "J5") (pin "1") (pinfunction "1_1") (pintype "passive"))
      (node (ref "Q1") (pin "3") (pinfunction "S_3") (pintype "passive"))
      (node (ref "Q2") (pin "3") (pinfunction "S_3") (pintype "passive"))
      (node (ref "Q3") (pin "3") (pinfunction "S_3") (pintype "passive"))
      (node (ref "Q4") (pin "3") (pinfunction "S_3") (pintype "passive"))
      (node (ref "Q5") (pin "2") (pinfunction "D_2") (pintype "passive"))
      (node (ref "Q6") (pin "2") (pinfunction "D_2") (pintype "passive"))
      (node (ref "Q7") (pin "2") (pinfunction "D_2") (pintype "passive"))
      (node (ref "Q8") (pin "2") (pinfunction "D_2") (pintype "passive"))
      (node (ref "R11") (pin "2") (pinfunction "2_2") (pintype "passive"))
      (node (ref "U1") (pin "14") (pinfunction "VSSA_14") (pintype "passive"))
    )
    (net (code "5") (name "/PHASE_V") (class "Default")
      (node (ref "C12") (pin "1") (pinfunction "1_1") (pintype "passive"))
      (node (ref "C13") (pin "1") (pinfunction "1_1") (pintype "passive"))
      (node (ref "J6") (pin "1") (pinfunction "1_1") (pintype "passive"))
      (node (ref "Q10") (pin "3") (pinfunction "S_3") (pintype "passive"))
      (node (ref "Q11") (pin "3") (pinfunction "S_3") (pintype "passive"))
      (node (ref "Q12") (pin "3") (pinfunction "S_3") (pintype "passive"))
      (node (ref "Q13") (pin "2") (pinfunction "D_2") (pintype "passive"))
      (node (ref "Q14") (pin "2") (pinfunction "D_2") (pintype "passive"))
      (node (ref "Q15") (pin "2") (pinfunction "D_2") (pintype "passive"))
      (node (ref "Q16") (pin "2") (pinfunction "D_2") (pintype "passive"))
      (node (ref "Q9") (pin "3") (pinfunction "S_3") (pintype "passive"))
      (node (ref "R30") (pin "2") (pinfunction "2_2") (pintype "passive"))
      (node (ref "U2") (pin "14") (pinfunction "VSSA_14") (pintype "passive"))
    )
    (net (code "6") (name "/PHASE_W") (class "Default")
      (node (ref "C23") (pin "1") (pinfunction "1_1") (pintype "passive"))
      (node (ref "C24") (pin "1") (pinfunction "1_1") (pintype "passive"))
      (node (ref "J7") (pin "1") (pinfunction "1_1") (pintype "passive"))
      (node (ref "Q17") (pin "3") (pinfunction "S_3") (pintype "passive"))
      (node (ref "Q18") (pin "3") (pinfunction "S_3") (pintype "passive"))
      (node (ref "Q19") (pin "3") (pinfunction "S_3") (pintype "passive"))
      (node (ref "Q20") (pin "3") (pinfunction "S_3") (pintype "passive"))
      (node (ref "Q21") (pin "2") (pinfunction "D_2") (pintype "passive"))
      (node (ref "Q22") (pin "2") (pinfunction "D_2") (pintype "passive"))
      (node (ref "Q23") (pin "2") (pinfunction "D_2") (pintype "passive"))
      (node (ref "Q24") (pin "2") (pinfunction "D_2") (pintype "passive"))
      (node (ref "R49") (pin "2") (pinfunction "2_2") (pintype "passive"))
      (node (ref "U3") (pin "14") (pinfunction "VSSA_14") (pintype "passive"))
    )
    (net (code "7") (name "/PWM_U_A") (class "Default")
      (node (ref "J3") (pin "2") (pinfunction "2_2") (pintype "passive"))
      (node (ref "R9") (pin "1") (pinfunction "1_1") (pintype "passive"))
    )
    (net (code "8") (name "/PWM_U_B") (class "Default")
      (node (ref "J3") (pin "7") (pinfunction "7_7") (pintype "passive"))
      (node (ref "R10") (pin "1") (pinfunction "1_1") (pintype "passive"))
    )
    (net (code "9") (name "/PWM_V_A") (class "Default")
      (node (ref "J4") (pin "2") (pinfunction "2_2") (pintype "passive"))
      (node (ref "R28") (pin "1") (pinfunction "1_1") (pintype "passive"))
    )
    (net (code "10") (name "/PWM_V_B") (class "Default")
      (node (ref "J4") (pin "7") (pinfunction "7_7") (pintype "passive"))
      (node (ref "R29") (pin "1") (pinfunction "1_1") (pintype "passive"))
    )
    (net (code "11") (name "/PWM_W_A") (class "Default")
      (node (ref "J8") (pin "2") (pinfunction "2_2") (pintype "passive"))
      (node (ref "R47") (pin "1") (pinfunction "1_1") (pintype "passive"))
    )
    (net (code "12") (name "/PWM_W_B") (class "Default")
      (node (ref "J8") (pin "7") (pinfunction "7_7") (pintype "passive"))
      (node (ref "R48") (pin "1") (pinfunction "1_1") (pintype "passive"))
    )
    (net (code "13") (name "/Tsense_U") (class "Default")
      (node (ref "C11") (pin "2") (pinfunction "2_2") (pintype "passive"))
      (node (ref "J3") (pin "8") (pinfunction "8_8") (pintype "passive"))
      (node (ref "R19") (pin "2") (pinfunction "2_2") (pintype "passive"))
      (node (ref "TR1") (pin "1") (pinfunction "1_1") (pintype "passive"))
    )
    (net (code "14") (name "/Tsense_V") (class "Default")
      (node (ref "C18") (pin "2") (pinfunction "2_2") (pintype "passive"))
      (node (ref "J4") (pin "8") (pinfunction "8_8") (pintype "passive"))
      (node (ref "R38") (pin "2") (pinfunction "2_2") (pintype "passive"))
      (node (ref "TR2") (pin "1") (pinfunction "1_1") (pintype "passive"))
    )
    (net (code "15") (name "/Tsense_W") (class "Default")
      (node (ref "C29") (pin "2") (pinfunction "2_2") (pintype "passive"))
      (node (ref "J8") (pin "8") (pinfunction "8_8") (pintype "passive"))
      (node (ref "R57") (pin "2") (pinfunction "2_2") (pintype "passive"))
      (node (ref "TR3") (pin "1") (pinfunction "1_1") (pintype "passive"))
    )
    (net (code "16") (name "/Vsense_U") (class "Default")
      (node (ref "J3") (pin "1") (pinfunction "1_1") (pintype "passive"))
      (node (ref "R11") (pin "1") (pinfunction "1_1") (pintype "passive"))
      (node (ref "R13") (pin "2") (pinfunction "2_2") (pintype "passive"))
    )
    (net (code "17") (name "/Vsense_V") (class "Default")
      (node (ref "J4") (pin "1") (pinfunction "1_1") (pintype "passive"))
      (node (ref "R30") (pin "1") (pinfunction "1_1") (pintype "passive"))
      (node (ref "R32") (pin "2") (pinfunction "2_2") (pintype "passive"))
    )
    (net (code "18") (name "/Vsense_W") (class "Default")
      (node (ref "J8") (pin "1") (pinfunction "1_1") (pintype "passive"))
      (node (ref "R49") (pin "1") (pinfunction "1_1") (pintype "passive"))
      (node (ref "R51") (pin "2") (pinfunction "2_2") (pintype "passive"))
    )
    (net (code "19") (name "GND") (class "Default")
      (node (ref "C11") (pin "1") (pinfunction "1_1") (pintype "passive"))
      (node (ref "C17") (pin "1") (pinfunction "1_1") (pintype "passive"))
      (node (ref "C18") (pin "1") (pinfunction "1_1") (pintype "passive"))
      (node (ref "C19") (pin "1") (pinfunction "1_1") (pintype "passive"))
      (node (ref "C20") (pin "1") (pinfunction "1_1") (pintype "passive"))
      (node (ref "C28") (pin "1") (pinfunction "1_1") (pintype "passive"))
      (node (ref "C29") (pin "1") (pinfunction "1_1") (pintype "passive"))
      (node (ref "C30") (pin "1") (pinfunction "1_1") (pintype "passive"))
      (node (ref "C31") (pin "1") (pinfunction "1_1") (pintype "passive"))
      (node (ref "C6") (pin "1") (pinfunction "1_1") (pintype "passive"))
      (node (ref "C7") (pin "1") (pinfunction "1_1") (pintype "passive"))
      (node (ref "C8") (pin "1") (pinfunction "1_1") (pintype "passive"))
      (node (ref "J3") (pin "5") (pinfunction "5_5") (pintype "passive"))
      (node (ref "J4") (pin "5") (pinfunction "5_5") (pintype "passive"))
      (node (ref "J8") (pin "5") (pinfunction "5_5") (pintype "passive"))
      (node (ref "R14") (pin "1") (pinfunction "1_1") (pintype "passive"))
      (node (ref "R19") (pin "1") (pinfunction "1_1") (pintype "passive"))
      (node (ref "R33") (pin "1") (pinfunction "1_1") (pintype "passive"))
      (node (ref "R38") (pin "1") (pinfunction "1_1") (pintype "passive"))
      (node (ref "R52") (pin "1") (pinfunction "1_1") (pintype "passive"))
      (node (ref "R57") (pin "1") (pinfunction "1_1") (pintype "passive"))
      (node (ref "U1") (pin "4") (pinfunction "GND_4") (pintype "passive"))
      (node (ref "U2") (pin "4") (pinfunction "GND_4") (pintype "passive"))
      (node (ref "U3") (pin "4") (pinfunction "GND_4") (pintype "passive"))
    )
    (net (code "20") (name "Net-(C3-Pad2)") (class "Default")
      (node (ref "C3") (pin "2") (pinfunction "2_2") (pintype "passive"))
      (node (ref "C4") (pin "2") (pinfunction "2_2") (pintype "passive"))
      (node (ref "C5") (pin "2") (pinfunction "2_2") (pintype "passive"))
      (node (ref "R6") (pin "2") (pinfunction "2_2") (pintype "passive"))
      (node (ref "R7") (pin "2") (pinfunction "2_2") (pintype "passive"))
      (node (ref "R8") (pin "2") (pinfunction "2_2") (pintype "passive"))
    )
    (net (code "21") (name "Net-(C14-Pad2)") (class "Default")
      (node (ref "C14") (pin "2") (pinfunction "2_2") (pintype "passive"))
      (node (ref "C15") (pin "2") (pinfunction "2_2") (pintype "passive"))
      (node (ref "C16") (pin "2") (pinfunction "2_2") (pintype "passive"))
      (node (ref "R25") (pin "2") (pinfunction "2_2") (pintype "passive"))
      (node (ref "R26") (pin "2") (pinfunction "2_2") (pintype "passive"))
      (node (ref "R27") (pin "2") (pinfunction "2_2") (pintype "passive"))
    )
    (net (code "22") (name "Net-(C25-Pad2)") (class "Default")
      (node (ref "C25") (pin "2") (pinfunction "2_2") (pintype "passive"))
      (node (ref "C26") (pin "2") (pinfunction "2_2") (pintype "passive"))
      (node (ref "C27") (pin "2") (pinfunction "2_2") (pintype "passive"))
      (node (ref "R44") (pin "2") (pinfunction "2_2") (pintype "passive"))
      (node (ref "R45") (pin "2") (pinfunction "2_2") (pintype "passive"))
      (node (ref "R46") (pin "2") (pinfunction "2_2") (pintype "passive"))
    )
    (net (code "23") (name "Net-(D1-K)") (class "Default")
      (node (ref "C1") (pin "2") (pinfunction "2_2") (pintype "passive"))
      (node (ref "C2") (pin "2") (pinfunction "2_2") (pintype "passive"))
      (node (ref "D1") (pin "C") (pinfunction "K_C") (pintype "passive"))
      (node (ref "U1") (pin "16") (pinfunction "VDDA_16") (pintype "passive"))
    )
    (net (code "24") (name "Net-(D1-PadA)") (class "Default")
      (node (ref "D1") (pin "A") (pinfunction "A_A") (pintype "passive"))
      (node (ref "R1") (pin "2") (pinfunction "2_2") (pintype "passive"))
    )
    (net (code "25") (name "Net-(D2-K)") (class "Default")
      (node (ref "C12") (pin "2") (pinfunction "2_2") (pintype "passive"))
      (node (ref "C13") (pin "2") (pinfunction "2_2") (pintype "passive"))
      (node (ref "D2") (pin "C") (pinfunction "K_C") (pintype "passive"))
      (node (ref "U2") (pin "16") (pinfunction "VDDA_16") (pintype "passive"))
    )
    (net (code "26") (name "Net-(D2-PadA)") (class "Default")
      (node (ref "D2") (pin "A") (pinfunction "A_A") (pintype "passive"))
      (node (ref "R20") (pin "2") (pinfunction "2_2") (pintype "passive"))
    )
    (net (code "27") (name "Net-(D3-K)") (class "Default")
      (node (ref "C23") (pin "2") (pinfunction "2_2") (pintype "passive"))
      (node (ref "C24") (pin "2") (pinfunction "2_2") (pintype "passive"))
      (node (ref "D3") (pin "C") (pinfunction "K_C") (pintype "passive"))
      (node (ref "U3") (pin "16") (pinfunction "VDDA_16") (pintype "passive"))
    )
    (net (code "28") (name "Net-(D3-PadA)") (class "Default")
      (node (ref "D3") (pin "A") (pinfunction "A_A") (pintype "passive"))
      (node (ref "R39") (pin "2") (pinfunction "2_2") (pintype "passive"))
    )
    (net (code "29") (name "Net-(Q1-G)") (class "Default")
      (node (ref "Q1") (pin "1") (pinfunction "G_1") (pintype "passive"))
      (node (ref "R5") (pin "1") (pinfunction "1_1") (pintype "passive"))
    )
    (net (code "30") (name "Net-(Q2-G)") (class "Default")
      (node (ref "Q2") (pin "1") (pinfunction "G_1") (pintype "passive"))
      (node (ref "R2") (pin "1") (pinfunction "1_1") (pintype "passive"))
    )
    (net (code "31") (name "Net-(Q3-G)") (class "Default")
      (node (ref "Q3") (pin "1") (pinfunction "G_1") (pintype "passive"))
      (node (ref "R3") (pin "1") (pinfunction "1_1") (pintype "passive"))
    )
    (net (code "32") (name "Net-(Q4-G)") (class "Default")
      (node (ref "Q4") (pin "1") (pinfunction "G_1") (pintype "passive"))
      (node (ref "R4") (pin "1") (pinfunction "1_1") (pintype "passive"))
    )
    (net (code "33") (name "Net-(Q5-G)") (class "Default")
      (node (ref "Q5") (pin "1") (pinfunction "G_1") (pintype "passive"))
      (node (ref "R17") (pin "2") (pinfunction "2_2") (pintype "passive"))
    )
    (net (code "34") (name "Net-(Q6-G)") (class "Default")
      (node (ref "Q6") (pin "1") (pinfunction "G_1") (pintype "passive"))
      (node (ref "R18") (pin "2") (pinfunction "2_2") (pintype "passive"))
    )
    (net (code "35") (name "Net-(Q7-G)") (class "Default")
      (node (ref "Q7") (pin "1") (pinfunction "G_1") (pintype "passive"))
      (node (ref "R15") (pin "2") (pinfunction "2_2") (pintype "passive"))
    )
    (net (code "36") (name "Net-(Q8-G)") (class "Default")
      (node (ref "Q8") (pin "1") (pinfunction "G_1") (pintype "passive"))
      (node (ref "R16") (pin "2") (pinfunction "2_2") (pintype "passive"))
    )
    (net (code "37") (name "Net-(Q9-G)") (class "Default")
      (node (ref "Q9") (pin "1") (pinfunction "G_1") (pintype "passive"))
      (node (ref "R24") (pin "1") (pinfunction "1_1") (pintype "passive"))
    )
    (net (code "38") (name "Net-(Q10-G)") (class "Default")
      (node (ref "Q10") (pin "1") (pinfunction "G_1") (pintype "passive"))
      (node (ref "R21") (pin "1") (pinfunction "1_1") (pintype "passive"))
    )
    (net (code "39") (name "Net-(Q11-G)") (class "Default")
      (node (ref "Q11") (pin "1") (pinfunction "G_1") (pintype "passive"))
      (node (ref "R22") (pin "1") (pinfunction "1_1") (pintype "passive"))
    )
    (net (code "40") (name "Net-(Q12-G)") (class "Default")
      (node (ref "Q12") (pin "1") (pinfunction "G_1") (pintype "passive"))
      (node (ref "R23") (pin "1") (pinfunction "1_1") (pintype "passive"))
    )
    (net (code "41") (name "Net-(Q13-G)") (class "Default")
      (node (ref "Q13") (pin "1") (pinfunction "G_1") (pintype "passive"))
      (node (ref "R36") (pin "2") (pinfunction "2_2") (pintype "passive"))
    )
    (net (code "42") (name "Net-(Q14-G)") (class "Default")
      (node (ref "Q14") (pin "1") (pinfunction "G_1") (pintype "passive"))
      (node (ref "R37") (pin "2") (pinfunction "2_2") (pintype "passive"))
    )
    (net (code "43") (name "Net-(Q15-G)") (class "Default")
      (node (ref "Q15") (pin "1") (pinfunction "G_1") (pintype "passive"))
      (node (ref "R34") (pin "2") (pinfunction "2_2") (pintype "passive"))
    )
    (net (code "44") (name "Net-(Q16-G)") (class "Default")
      (node (ref "Q16") (pin "1") (pinfunction "G_1") (pintype "passive"))
      (node (ref "R35") (pin "2") (pinfunction "2_2") (pintype "passive"))
    )
    (net (code "45") (name "Net-(Q17-G)") (class "Default")
      (node (ref "Q17") (pin "1") (pinfunction "G_1") (pintype "passive"))
      (node (ref "R43") (pin "1") (pinfunction "1_1") (pintype "passive"))
    )
    (net (code "46") (name "Net-(Q18-G)") (class "Default")
      (node (ref "Q18") (pin "1") (pinfunction "G_1") (pintype "passive"))
      (node (ref "R40") (pin "1") (pinfunction "1_1") (pintype "passive"))
    )
    (net (code "47") (name "Net-(Q19-G)") (class "Default")
      (node (ref "Q19") (pin "1") (pinfunction "G_1") (pintype "passive"))
      (node (ref "R41") (pin "1") (pinfunction "1_1") (pintype "passive"))
    )
    (net (code "48") (name "Net-(Q20-G)") (class "Default")
      (node (ref "Q20") (pin "1") (pinfunction "G_1") (pintype "passive"))
      (node (ref "R42") (pin "1") (pinfunction "1_1") (pintype "passive"))
    )
    (net (code "49") (name "Net-(Q21-G)") (class "Default")
      (node (ref "Q21") (pin "1") (pinfunction "G_1") (pintype "passive"))
      (node (ref "R53") (pin "2") (pinfunction "2_2") (pintype "passive"))
    )
    (net (code "50") (name "Net-(Q22-G)") (class "Default")
      (node (ref "Q22") (pin "1") (pinfunction "G_1") (pintype "passive"))
      (node (ref "R54") (pin "2") (pinfunction "2_2") (pintype "passive"))
    )
    (net (code "51") (name "Net-(Q23-G)") (class "Default")
      (node (ref "Q23") (pin "1") (pinfunction "G_1") (pintype "passive"))
      (node (ref "R55") (pin "2") (pinfunction "2_2") (pintype "passive"))
    )
    (net (code "52") (name "Net-(Q24-G)") (class "Default")
      (node (ref "Q24") (pin "1") (pinfunction "G_1") (pintype "passive"))
      (node (ref "R56") (pin "2") (pinfunction "2_2") (pintype "passive"))
    )
    (net (code "53") (name "Net-(U1-DISABLE)") (class "Default")
      (node (ref "C3") (pin "1") (pinfunction "1_1") (pintype "passive"))
      (node (ref "R12") (pin "2") (pinfunction "2_2") (pintype "passive"))
      (node (ref "R6") (pin "1") (pinfunction "1_1") (pintype "passive"))
      (node (ref "U1") (pin "5") (pinfunction "DISABLE_5") (pintype "passive"))
    )
    (net (code "54") (name "Net-(U1-DT)") (class "Default")
      (node (ref "C6") (pin "2") (pinfunction "2_2") (pintype "passive"))
      (node (ref "R14") (pin "2") (pinfunction "2_2") (pintype "passive"))
      (node (ref "U1") (pin "6") (pinfunction "DT_6") (pintype "passive"))
    )
    (net (code "55") (name "Net-(U1-INA)") (class "Default")
      (node (ref "C5") (pin "1") (pinfunction "1_1") (pintype "passive"))
      (node (ref "R8") (pin "1") (pinfunction "1_1") (pintype "passive"))
      (node (ref "R9") (pin "2") (pinfunction "2_2") (pintype "passive"))
      (node (ref "U1") (pin "1") (pinfunction "INA_1") (pintype "passive"))
    )
    (net (code "56") (name "Net-(U1-INB)") (class "Default")
      (node (ref "C4") (pin "1") (pinfunction "1_1") (pintype "passive"))
      (node (ref "R10") (pin "2") (pinfunction "2_2") (pintype "passive"))
      (node (ref "R7") (pin "1") (pinfunction "1_1") (pintype "passive"))
      (node (ref "U1") (pin "2") (pinfunction "INB_2") (pintype "passive"))
    )
    (net (code "57") (name "Net-(U1-OUTA)") (class "Default")
      (node (ref "R2") (pin "2") (pinfunction "2_2") (pintype "passive"))
      (node (ref "R3") (pin "2") (pinfunction "2_2") (pintype "passive"))
      (node (ref "R4") (pin "2") (pinfunction "2_2") (pintype "passive"))
      (node (ref "R5") (pin "2") (pinfunction "2_2") (pintype "passive"))
      (node (ref "U1") (pin "15") (pinfunction "OUTA_15") (pintype "passive"))
    )
    (net (code "58") (name "Net-(U1-OUTB)") (class "Default")
      (node (ref "R15") (pin "1") (pinfunction "1_1") (pintype "passive"))
      (node (ref "R16") (pin "1") (pinfunction "1_1") (pintype "passive"))
      (node (ref "R17") (pin "1") (pinfunction "1_1") (pintype "passive"))
      (node (ref "R18") (pin "1") (pinfunction "1_1") (pintype "passive"))
      (node (ref "U1") (pin "10") (pinfunction "OUTB_10") (pintype "passive"))
    )
    (net (code "59") (name "Net-(U2-DISABLE)") (class "Default")
      (node (ref "C14") (pin "1") (pinfunction "1_1") (pintype "passive"))
      (node (ref "R25") (pin "1") (pinfunction "1_1") (pintype "passive"))
      (node (ref "R31") (pin "2") (pinfunction "2_2") (pintype "passive"))
      (node (ref "U2") (pin "5") (pinfunction "DISABLE_5") (pintype "passive"))
    )
    (net (code "60") (name "Net-(U2-DT)") (class "Default")
      (node (ref "C17") (pin "2") (pinfunction "2_2") (pintype "passive"))
      (node (ref "R33") (pin "2") (pinfunction "2_2") (pintype "passive"))
      (node (ref "U2") (pin "6") (pinfunction "DT_6") (pintype "passive"))
    )
    (net (code "61") (name "Net-(U2-INA)") (class "Default")
      (node (ref "C16") (pin "1") (pinfunction "1_1") (pintype "passive"))
      (node (ref "R27") (pin "1") (pinfunction "1_1") (pintype "passive"))
      (node (ref "R28") (pin "2") (pinfunction "2_2") (pintype "passive"))
      (node (ref "U2") (pin "1") (pinfunction "INA_1") (pintype "passive"))
    )
    (net (code "62") (name "Net-(U2-INB)") (class "Default")
      (node (ref "C15") (pin "1") (pinfunction "1_1") (pintype "passive"))
      (node (ref "R26") (pin "1") (pinfunction "1_1") (pintype "passive"))
      (node (ref "R29") (pin "2") (pinfunction "2_2") (pintype "passive"))
      (node (ref "U2") (pin "2") (pinfunction "INB_2") (pintype "passive"))
    )
    (net (code "63") (name "Net-(U2-OUTA)") (class "Default")
      (node (ref "R21") (pin "2") (pinfunction "2_2") (pintype "passive"))
      (node (ref "R22") (pin "2") (pinfunction "2_2") (pintype "passive"))
      (node (ref "R23") (pin "2") (pinfunction "2_2") (pintype "passive"))
      (node (ref "R24") (pin "2") (pinfunction "2_2") (pintype "passive"))
      (node (ref "U2") (pin "15") (pinfunction "OUTA_15") (pintype "passive"))
    )
    (net (code "64") (name "Net-(U2-OUTB)") (class "Default")
      (node (ref "R34") (pin "1") (pinfunction "1_1") (pintype "passive"))
      (node (ref "R35") (pin "1") (pinfunction "1_1") (pintype "passive"))
      (node (ref "R36") (pin "1") (pinfunction "1_1") (pintype "passive"))
      (node (ref "R37") (pin "1") (pinfunction "1_1") (pintype "passive"))
      (node (ref "U2") (pin "10") (pinfunction "OUTB_10") (pintype "passive"))
    )
    (net (code "65") (name "Net-(U3-DISABLE)") (class "Default")
      (node (ref "C25") (pin "1") (pinfunction "1_1") (pintype "passive"))
      (node (ref "R44") (pin "1") (pinfunction "1_1") (pintype "passive"))
      (node (ref "R50") (pin "2") (pinfunction "2_2") (pintype "passive"))
      (node (ref "U3") (pin "5") (pinfunction "DISABLE_5") (pintype "passive"))
    )
    (net (code "66") (name "Net-(U3-DT)") (class "Default")
      (node (ref "C28") (pin "2") (pinfunction "2_2") (pintype "passive"))
      (node (ref "R52") (pin "2") (pinfunction "2_2") (pintype "passive"))
      (node (ref "U3") (pin "6") (pinfunction "DT_6") (pintype "passive"))
    )
    (net (code "67") (name "Net-(U3-INA)") (class "Default")
      (node (ref "C27") (pin "1") (pinfunction "1_1") (pintype "passive"))
      (node (ref "R46") (pin "1") (pinfunction "1_1") (pintype "passive"))
      (node (ref "R47") (pin "2") (pinfunction "2_2") (pintype "passive"))
      (node (ref "U3") (pin "1") (pinfunction "INA_1") (pintype "passive"))
    )
    (net (code "68") (name "Net-(U3-INB)") (class "Default")
      (node (ref "C26") (pin "1") (pinfunction "1_1") (pintype "passive"))
      (node (ref "R45") (pin "1") (pinfunction "1_1") (pintype "passive"))
      (node (ref "R48") (pin "2") (pinfunction "2_2") (pintype "passive"))
      (node (ref "U3") (pin "2") (pinfunction "INB_2") (pintype "passive"))
    )
    (net (code "69") (name "Net-(U3-OUTA)") (class "Default")
      (node (ref "R40") (pin "2") (pinfunction "2_2") (pintype "passive"))
      (node (ref "R41") (pin "2") (pinfunction "2_2") (pintype "passive"))
      (node (ref "R42") (pin "2") (pinfunction "2_2") (pintype "passive"))
      (node (ref "R43") (pin "2") (pinfunction "2_2") (pintype "passive"))
      (node (ref "U3") (pin "15") (pinfunction "OUTA_15") (pintype "passive"))
    )
    (net (code "70") (name "Net-(U3-OUTB)") (class "Default")
      (node (ref "R53") (pin "1") (pinfunction "1_1") (pintype "passive"))
      (node (ref "R54") (pin "1") (pinfunction "1_1") (pintype "passive"))
      (node (ref "R55") (pin "1") (pinfunction "1_1") (pintype "passive"))
      (node (ref "R56") (pin "1") (pinfunction "1_1") (pintype "passive"))
      (node (ref "U3") (pin "10") (pinfunction "OUTB_10") (pintype "passive"))
    )
    (net (code "71") (name "V+") (class "Default")
      (node (ref "J1") (pin "1") (pinfunction "1_1") (pintype "passive"))
      (node (ref "Q1") (pin "2") (pinfunction "D_2") (pintype "passive"))
      (node (ref "Q10") (pin "2") (pinfunction "D_2") (pintype "passive"))
      (node (ref "Q11") (pin "2") (pinfunction "D_2") (pintype "passive"))
      (node (ref "Q12") (pin "2") (pinfunction "D_2") (pintype "passive"))
      (node (ref "Q17") (pin "2") (pinfunction "D_2") (pintype "passive"))
      (node (ref "Q18") (pin "2") (pinfunction "D_2") (pintype "passive"))
      (node (ref "Q19") (pin "2") (pinfunction "D_2") (pintype "passive"))
      (node (ref "Q2") (pin "2") (pinfunction "D_2") (pintype "passive"))
      (node (ref "Q20") (pin "2") (pinfunction "D_2") (pintype "passive"))
      (node (ref "Q3") (pin "2") (pinfunction "D_2") (pintype "passive"))
      (node (ref "Q4") (pin "2") (pinfunction "D_2") (pintype "passive"))
      (node (ref "Q9") (pin "2") (pinfunction "D_2") (pintype "passive"))
    )
    (net (code "72") (name "V-") (class "Default")
      (node (ref "C10") (pin "1") (pinfunction "1_1") (pintype "passive"))
      (node (ref "C21") (pin "1") (pinfunction "1_1") (pintype "passive"))
      (node (ref "C22") (pin "1") (pinfunction "1_1") (pintype "passive"))
      (node (ref "C32") (pin "1") (pinfunction "1_1") (pintype "passive"))
      (node (ref "C33") (pin "1") (pinfunction "1_1") (pintype "passive"))
      (node (ref "C9") (pin "1") (pinfunction "1_1") (pintype "passive"))
      (node (ref "J2") (pin "1") (pinfunction "1_1") (pintype "passive"))
      (node (ref "Q13") (pin "3") (pinfunction "S_3") (pintype "passive"))
      (node (ref "Q15") (pin "3") (pinfunction "S_3") (pintype "passive"))
      (node (ref "Q16") (pin "3") (pinfunction "S_3") (pintype "passive"))
      (node (ref "Q21") (pin "3") (pinfunction "S_3") (pintype "passive"))
      (node (ref "Q22") (pin "3") (pinfunction "S_3") (pintype "passive"))
      (node (ref "Q23") (pin "3") (pinfunction "S_3") (pintype "passive"))
      (node (ref "Q24") (pin "3") (pinfunction "S_3") (pintype "passive"))
      (node (ref "Q5") (pin "3") (pinfunction "S_3") (pintype "passive"))
      (node (ref "Q6") (pin "3") (pinfunction "S_3") (pintype "passive"))
      (node (ref "Q7") (pin "3") (pinfunction "S_3") (pintype "passive"))
      (node (ref "Q8") (pin "3") (pinfunction "S_3") (pintype "passive"))
      (node (ref "R13") (pin "1") (pinfunction "1_1") (pintype "passive"))
      (node (ref "R32") (pin "1") (pinfunction "1_1") (pintype "passive"))
      (node (ref "R51") (pin "1") (pinfunction "1_1") (pintype "passive"))
      (node (ref "U1") (pin "9") (pinfunction "VSSB_9") (pintype "passive"))
      (node (ref "U2") (pin "9") (pinfunction "VSSB_9") (pintype "passive"))
      (node (ref "U3") (pin "9") (pinfunction "VSSB_9") (pintype "passive"))
    )
    (net (code "73") (name "unconnected-(Q14-S-Pad3)") (class "Default")
      (node (ref "Q14") (pin "3") (pinfunction "S_3") (pintype "passive"))
    )
    (net (code "74") (name "unconnected-(U1-NC_1-Pad7)") (class "Default")
      (node (ref "U1") (pin "7") (pinfunction "NC_1_7") (pintype "passive"))
    )
    (net (code "75") (name "unconnected-(U1-NC_2-Pad12)") (class "Default")
      (node (ref "U1") (pin "12") (pinfunction "NC_2_12") (pintype "passive"))
    )
    (net (code "76") (name "unconnected-(U1-NC_3-Pad13)") (class "Default")
      (node (ref "U1") (pin "13") (pinfunction "NC_3_13") (pintype "passive"))
    )
    (net (code "77") (name "unconnected-(U2-NC_1-Pad7)") (class "Default")
      (node (ref "U2") (pin "7") (pinfunction "NC_1_7") (pintype "passive"))
    )
    (net (code "78") (name "unconnected-(U2-NC_2-Pad12)") (class "Default")
      (node (ref "U2") (pin "12") (pinfunction "NC_2_12") (pintype "passive"))
    )
    (net (code "79") (name "unconnected-(U2-NC_3-Pad13)") (class "Default")
      (node (ref "U2") (pin "13") (pinfunction "NC_3_13") (pintype "passive"))
    )
    (net (code "80") (name "unconnected-(U3-NC_1-Pad7)") (class "Default")
      (node (ref "U3") (pin "7") (pinfunction "NC_1_7") (pintype "passive"))
    )
    (net (code "81") (name "unconnected-(U3-NC_2-Pad12)") (class "Default")
      (node (ref "U3") (pin "12") (pinfunction "NC_2_12") (pintype "passive"))
    )
    (net (code "82") (name "unconnected-(U3-NC_3-Pad13)") (class "Default")
      (node (ref "U3") (pin "13") (pinfunction "NC_3_13") (pintype "passive"))
    )
  )
)
